# imu_03_12_2018.net
KiCad netlist of a schematic drawn in EAGLE
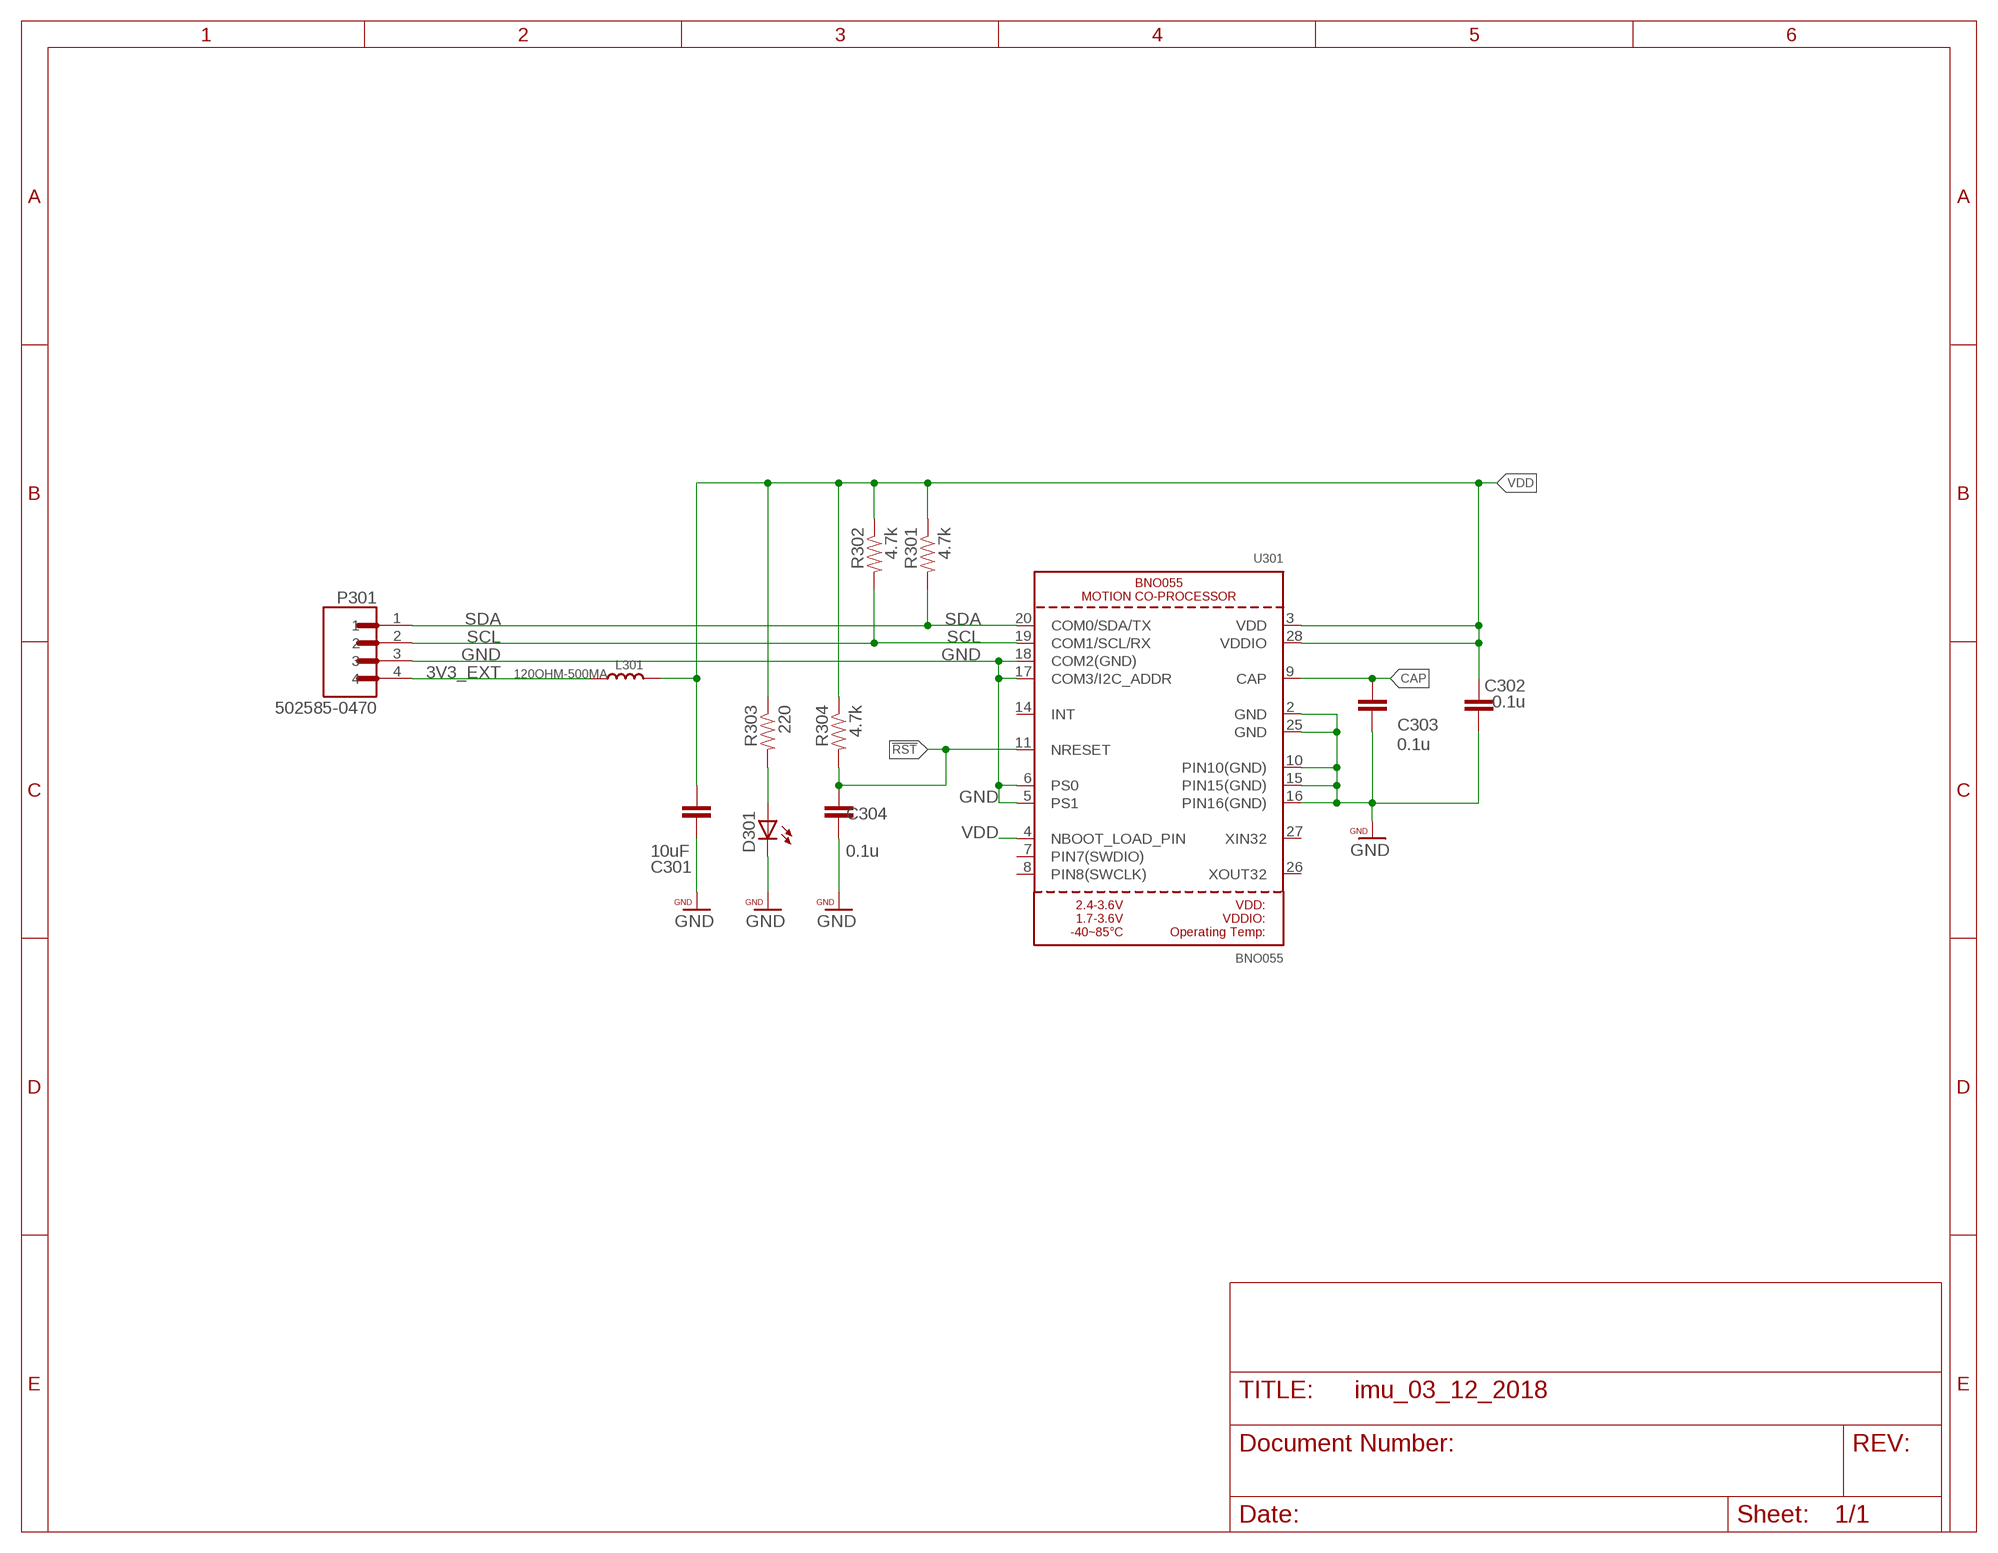
[diagram p0: schematic, sheet 1]

(export (version "E")
  (design (tool "Eeschema 10.0.6"))
  (components
    (comp (ref "C301")
      (value "10uF")
      (footprint "eagle-import:0402-CAP")
      (libsource (lib "eagle-import") (part "CAP0402-CAP"))
    )
    (comp (ref "C302")
      (value "0.1u")
      (footprint "eagle-import:0402-CAP")
      (libsource (lib "eagle-import") (part "CAP0402-CAP"))
    )
    (comp (ref "C303")
      (value "0.1u")
      (footprint "eagle-import:0402-CAP")
      (libsource (lib "eagle-import") (part "CAP0402-CAP"))
    )
    (comp (ref "C304")
      (value "0.1u")
      (footprint "eagle-import:0402-CAP")
      (libsource (lib "eagle-import") (part "CAP0402-CAP"))
    )
    (comp (ref "D301")
      (value "LEDCHIP-LED0603")
      (footprint "eagle-import:CHIP-LED0603")
      (libsource (lib "eagle-import") (part "LEDCHIP-LED0603"))
    )
    (comp (ref "L301")
      (value "120OHM-500MA")
      (footprint "eagle-import:L0603")
      (fields (field (name "MPN") "BLM18AG121SN1D"))
      (libsource (lib "eagle-import") (part "SMD-FERRITE-CHIP-120-OHM-500MA(0603)"))
    )
    (comp (ref "P301")
      (value "502585-0470")
      (footprint "eagle-import:MOLEX_502585-0470")
      (fields (field (name "MF") "Molex"))
      (libsource (lib "eagle-import") (part "502585-0470"))
    )
    (comp (ref "R301")
      (value "4.7k")
      (footprint "eagle-import:EIA-0402")
      (libsource (lib "eagle-import") (part "RESISTOR0402-TYP"))
    )
    (comp (ref "R302")
      (value "4.7k")
      (footprint "eagle-import:EIA-0402")
      (libsource (lib "eagle-import") (part "RESISTOR0402-TYP"))
    )
    (comp (ref "R303")
      (value "220")
      (footprint "eagle-import:EIA-0402")
      (libsource (lib "eagle-import") (part "RESISTOR0402-TYP"))
    )
    (comp (ref "R304")
      (value "4.7k")
      (footprint "eagle-import:EIA-0402")
      (libsource (lib "eagle-import") (part "RESISTOR0402-TYP"))
    )
    (comp (ref "U301")
      (value "BNO055")
      (footprint "eagle-import:BNO055")
      (libsource (lib "eagle-import") (part "BNO055"))
    )
  )
  (nets
    (net (code "1") (name "/3V3_EXT") (class "Default")
      (node (ref "L301") (pin "2") (pinfunction "2_2") (pintype "passive"))
      (node (ref "P301") (pin "4") (pinfunction "4_4") (pintype "passive"))
    )
    (net (code "2") (name "/SCL") (class "Default")
      (node (ref "P301") (pin "2") (pinfunction "2_2") (pintype "passive"))
      (node (ref "R302") (pin "2") (pinfunction "2_2") (pintype "passive"))
      (node (ref "U301") (pin "19") (pinfunction "COM1/SCL/RX_19") (pintype "bidirectional"))
    )
    (net (code "3") (name "/SDA") (class "Default")
      (node (ref "P301") (pin "1") (pinfunction "1_1") (pintype "passive"))
      (node (ref "R301") (pin "2") (pinfunction "2_2") (pintype "passive"))
      (node (ref "U301") (pin "20") (pinfunction "COM0/SDA/TX_20") (pintype "bidirectional"))
    )
    (net (code "4") (name "/~{RST}") (class "Default")
      (node (ref "C304") (pin "1") (pinfunction "1_1") (pintype "passive"))
      (node (ref "R304") (pin "2") (pinfunction "2_2") (pintype "passive"))
      (node (ref "U301") (pin "11") (pinfunction "NRESET_11") (pintype "bidirectional"))
    )
    (net (code "5") (name "CAP") (class "Default")
      (node (ref "C303") (pin "1") (pinfunction "1_1") (pintype "passive"))
      (node (ref "U301") (pin "9") (pinfunction "CAP_9") (pintype "passive"))
    )
    (net (code "6") (name "GND") (class "Default")
      (node (ref "C301") (pin "2") (pinfunction "2_2") (pintype "passive"))
      (node (ref "C302") (pin "2") (pinfunction "2_2") (pintype "passive"))
      (node (ref "C303") (pin "2") (pinfunction "2_2") (pintype "passive"))
      (node (ref "C304") (pin "2") (pinfunction "2_2") (pintype "passive"))
      (node (ref "D301") (pin "C") (pinfunction "C_C") (pintype "passive"))
      (node (ref "P301") (pin "3") (pinfunction "3_3") (pintype "passive"))
      (node (ref "U301") (pin "10") (pinfunction "PIN10(GND)_10") (pintype "bidirectional"))
      (node (ref "U301") (pin "15") (pinfunction "PIN15(GND)_15") (pintype "bidirectional"))
      (node (ref "U301") (pin "16") (pinfunction "PIN16(GND)_16") (pintype "bidirectional"))
      (node (ref "U301") (pin "17") (pinfunction "COM3/I2C_ADDR_17") (pintype "bidirectional"))
      (node (ref "U301") (pin "18") (pinfunction "COM2(GND)_18") (pintype "bidirectional"))
      (node (ref "U301") (pin "2") (pinfunction "GND_2") (pintype "power_in"))
      (node (ref "U301") (pin "25") (pinfunction "GND_25") (pintype "power_in"))
      (node (ref "U301") (pin "5") (pinfunction "PS1_5") (pintype "input"))
      (node (ref "U301") (pin "6") (pinfunction "PS0_6") (pintype "input"))
    )
    (net (code "7") (name "Net-(D301-PadA)") (class "Default")
      (node (ref "D301") (pin "A") (pinfunction "A_A") (pintype "passive"))
      (node (ref "R303") (pin "2") (pinfunction "2_2") (pintype "passive"))
    )
    (net (code "8") (name "VDD") (class "Default")
      (node (ref "C301") (pin "1") (pinfunction "1_1") (pintype "passive"))
      (node (ref "C302") (pin "1") (pinfunction "1_1") (pintype "passive"))
      (node (ref "L301") (pin "1") (pinfunction "1_1") (pintype "passive"))
      (node (ref "R301") (pin "1") (pinfunction "1_1") (pintype "passive"))
      (node (ref "R302") (pin "1") (pinfunction "1_1") (pintype "passive"))
      (node (ref "R303") (pin "1") (pinfunction "1_1") (pintype "passive"))
      (node (ref "R304") (pin "1") (pinfunction "1_1") (pintype "passive"))
      (node (ref "U301") (pin "28") (pinfunction "VDDIO_28") (pintype "power_in"))
      (node (ref "U301") (pin "3") (pinfunction "VDD_3") (pintype "power_in"))
      (node (ref "U301") (pin "4") (pinfunction "NBOOT_LOAD_PIN_4") (pintype "bidirectional"))
    )
    (net (code "9") (name "unconnected-(U301-INT-Pad14)") (class "Default")
      (node (ref "U301") (pin "14") (pinfunction "INT_14") (pintype "output"))
    )
    (net (code "10") (name "unconnected-(U301-PIN7(SWDIO)-Pad7)") (class "Default")
      (node (ref "U301") (pin "7") (pinfunction "PIN7(SWDIO)_7") (pintype "bidirectional"))
    )
    (net (code "11") (name "unconnected-(U301-PIN8(SWCLK)-Pad8)") (class "Default")
      (node (ref "U301") (pin "8") (pinfunction "PIN8(SWCLK)_8") (pintype "bidirectional"))
    )
    (net (code "12") (name "unconnected-(U301-XIN32-Pad27)") (class "Default")
      (node (ref "U301") (pin "27") (pinfunction "XIN32_27") (pintype "input"))
    )
    (net (code "13") (name "unconnected-(U301-XOUT32-Pad26)") (class "Default")
      (node (ref "U301") (pin "26") (pinfunction "XOUT32_26") (pintype "output"))
    )
  )
)
